# FPGA_NonIO.net
KiCad netlist of a schematic drawn in Altium Designer
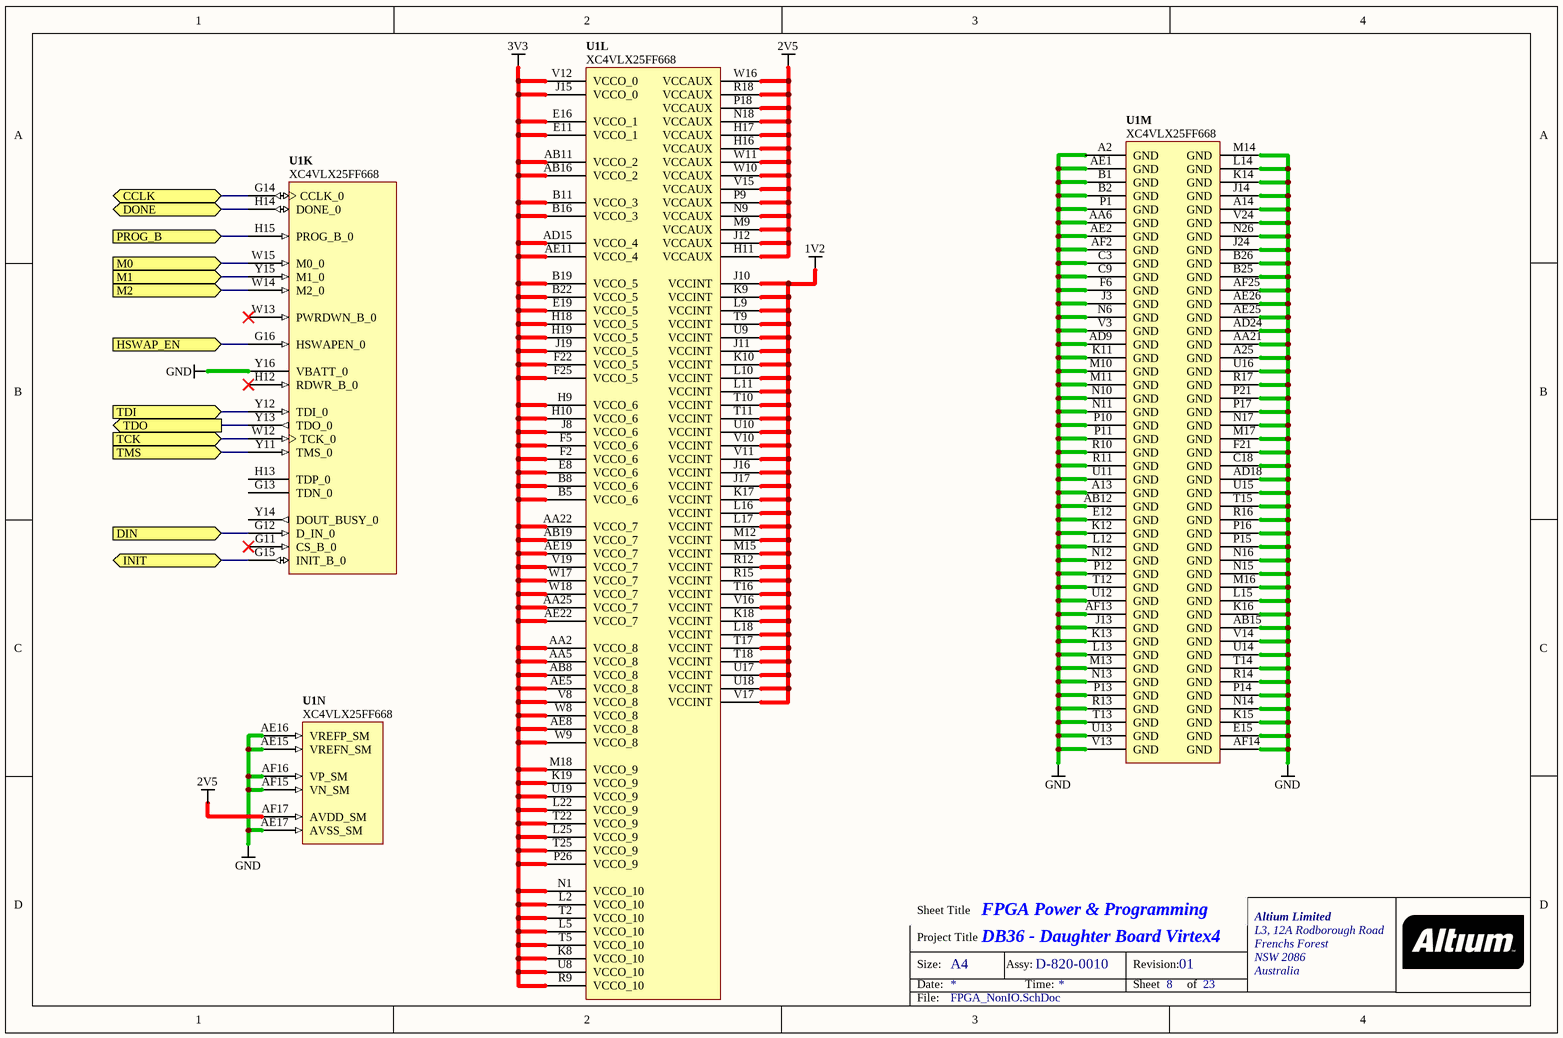
[diagram p0: FPGA_NonIO.SchDoc]

(export (version "E")
  (design (tool "Eeschema 10.0.6"))
  (components
    (comp (ref "U1")
      (value "XC4VLX25FF668")
      (footprint "XC4VLX25-10FF668C")
      (description "FPGA, Xilinx Virtex-4, XC4VLX25")
      (libsource (lib "AltiumDesignLibrary") (part "XC4VLX25-10FF668C"))
    )
  )
  (nets
    (net (code "1") (name "/CCLK") (class "Default")
      (node (ref "U1") (pin "G14") (pinfunction "CCLK_0_G14") (pintype "bidirectional"))
    )
    (net (code "2") (name "/DIN") (class "Default")
      (node (ref "U1") (pin "G12") (pinfunction "D_IN_0_G12") (pintype "input"))
    )
    (net (code "3") (name "/DONE") (class "Default")
      (node (ref "U1") (pin "H14") (pinfunction "DONE_0_H14") (pintype "bidirectional"))
    )
    (net (code "4") (name "/HSWAP_EN") (class "Default")
      (node (ref "U1") (pin "G16") (pinfunction "HSWAPEN_0_G16") (pintype "input"))
    )
    (net (code "5") (name "/INIT") (class "Default")
      (node (ref "U1") (pin "G15") (pinfunction "INIT_B_0_G15") (pintype "bidirectional"))
    )
    (net (code "6") (name "/M0") (class "Default")
      (node (ref "U1") (pin "W15") (pinfunction "M0_0_W15") (pintype "input"))
    )
    (net (code "7") (name "/M1") (class "Default")
      (node (ref "U1") (pin "Y15") (pinfunction "M1_0_Y15") (pintype "input"))
    )
    (net (code "8") (name "/M2") (class "Default")
      (node (ref "U1") (pin "W14") (pinfunction "M2_0_W14") (pintype "input"))
    )
    (net (code "9") (name "/PROG_B") (class "Default")
      (node (ref "U1") (pin "H15") (pinfunction "PROG_B_0_H15") (pintype "input"))
    )
    (net (code "10") (name "/TCK") (class "Default")
      (node (ref "U1") (pin "W12") (pinfunction "TCK_0_W12") (pintype "input"))
    )
    (net (code "11") (name "/TDI") (class "Default")
      (node (ref "U1") (pin "Y12") (pinfunction "TDI_0_Y12") (pintype "input"))
    )
    (net (code "12") (name "/TDO") (class "Default")
      (node (ref "U1") (pin "Y13") (pinfunction "TDO_0_Y13") (pintype "output"))
    )
    (net (code "13") (name "/TMS") (class "Default")
      (node (ref "U1") (pin "Y11") (pinfunction "TMS_0_Y11") (pintype "input"))
    )
    (net (code "14") (name "1V2") (class "Default")
      (node (ref "U1") (pin "J10") (pinfunction "VCCINT_J10") (pintype "power_in"))
      (node (ref "U1") (pin "J11") (pinfunction "VCCINT_J11") (pintype "power_in"))
      (node (ref "U1") (pin "J16") (pinfunction "VCCINT_J16") (pintype "power_in"))
      (node (ref "U1") (pin "J17") (pinfunction "VCCINT_J17") (pintype "power_in"))
      (node (ref "U1") (pin "K10") (pinfunction "VCCINT_K10") (pintype "power_in"))
      (node (ref "U1") (pin "K17") (pinfunction "VCCINT_K17") (pintype "power_in"))
      (node (ref "U1") (pin "K18") (pinfunction "VCCINT_K18") (pintype "power_in"))
      (node (ref "U1") (pin "K9") (pinfunction "VCCINT_K9") (pintype "power_in"))
      (node (ref "U1") (pin "L10") (pinfunction "VCCINT_L10") (pintype "power_in"))
      (node (ref "U1") (pin "L11") (pinfunction "VCCINT_L11") (pintype "power_in"))
      (node (ref "U1") (pin "L16") (pinfunction "VCCINT_L16") (pintype "power_in"))
      (node (ref "U1") (pin "L17") (pinfunction "VCCINT_L17") (pintype "power_in"))
      (node (ref "U1") (pin "L18") (pinfunction "VCCINT_L18") (pintype "power_in"))
      (node (ref "U1") (pin "L9") (pinfunction "VCCINT_L9") (pintype "power_in"))
      (node (ref "U1") (pin "M12") (pinfunction "VCCINT_M12") (pintype "power_in"))
      (node (ref "U1") (pin "M15") (pinfunction "VCCINT_M15") (pintype "power_in"))
      (node (ref "U1") (pin "R12") (pinfunction "VCCINT_R12") (pintype "power_in"))
      (node (ref "U1") (pin "R15") (pinfunction "VCCINT_R15") (pintype "power_in"))
      (node (ref "U1") (pin "T10") (pinfunction "VCCINT_T10") (pintype "power_in"))
      (node (ref "U1") (pin "T11") (pinfunction "VCCINT_T11") (pintype "power_in"))
      (node (ref "U1") (pin "T16") (pinfunction "VCCINT_T16") (pintype "power_in"))
      (node (ref "U1") (pin "T17") (pinfunction "VCCINT_T17") (pintype "power_in"))
      (node (ref "U1") (pin "T18") (pinfunction "VCCINT_T18") (pintype "power_in"))
      (node (ref "U1") (pin "T9") (pinfunction "VCCINT_T9") (pintype "power_in"))
      (node (ref "U1") (pin "U10") (pinfunction "VCCINT_U10") (pintype "power_in"))
      (node (ref "U1") (pin "U17") (pinfunction "VCCINT_U17") (pintype "power_in"))
      (node (ref "U1") (pin "U18") (pinfunction "VCCINT_U18") (pintype "power_in"))
      (node (ref "U1") (pin "U9") (pinfunction "VCCINT_U9") (pintype "power_in"))
      (node (ref "U1") (pin "V10") (pinfunction "VCCINT_V10") (pintype "power_in"))
      (node (ref "U1") (pin "V11") (pinfunction "VCCINT_V11") (pintype "power_in"))
      (node (ref "U1") (pin "V16") (pinfunction "VCCINT_V16") (pintype "power_in"))
      (node (ref "U1") (pin "V17") (pinfunction "VCCINT_V17") (pintype "power_in"))
    )
    (net (code "15") (name "2V5") (class "Default")
      (node (ref "U1") (pin "AF17") (pinfunction "AVDD_SM_AF17") (pintype "input"))
      (node (ref "U1") (pin "H11") (pinfunction "VCCAUX_H11") (pintype "power_in"))
      (node (ref "U1") (pin "H16") (pinfunction "VCCAUX_H16") (pintype "power_in"))
      (node (ref "U1") (pin "H17") (pinfunction "VCCAUX_H17") (pintype "power_in"))
      (node (ref "U1") (pin "J12") (pinfunction "VCCAUX_J12") (pintype "power_in"))
      (node (ref "U1") (pin "M9") (pinfunction "VCCAUX_M9") (pintype "power_in"))
      (node (ref "U1") (pin "N18") (pinfunction "VCCAUX_N18") (pintype "power_in"))
      (node (ref "U1") (pin "N9") (pinfunction "VCCAUX_N9") (pintype "power_in"))
      (node (ref "U1") (pin "P18") (pinfunction "VCCAUX_P18") (pintype "power_in"))
      (node (ref "U1") (pin "P9") (pinfunction "VCCAUX_P9") (pintype "power_in"))
      (node (ref "U1") (pin "R18") (pinfunction "VCCAUX_R18") (pintype "power_in"))
      (node (ref "U1") (pin "V15") (pinfunction "VCCAUX_V15") (pintype "power_in"))
      (node (ref "U1") (pin "W10") (pinfunction "VCCAUX_W10") (pintype "power_in"))
      (node (ref "U1") (pin "W11") (pinfunction "VCCAUX_W11") (pintype "power_in"))
      (node (ref "U1") (pin "W16") (pinfunction "VCCAUX_W16") (pintype "power_in"))
    )
    (net (code "16") (name "3V3") (class "Default")
      (node (ref "U1") (pin "AA2") (pinfunction "VCCO_8_AA2") (pintype "power_in"))
      (node (ref "U1") (pin "AA22") (pinfunction "VCCO_7_AA22") (pintype "power_in"))
      (node (ref "U1") (pin "AA25") (pinfunction "VCCO_7_AA25") (pintype "power_in"))
      (node (ref "U1") (pin "AA5") (pinfunction "VCCO_8_AA5") (pintype "power_in"))
      (node (ref "U1") (pin "AB11") (pinfunction "VCCO_2_AB11") (pintype "power_in"))
      (node (ref "U1") (pin "AB16") (pinfunction "VCCO_2_AB16") (pintype "power_in"))
      (node (ref "U1") (pin "AB19") (pinfunction "VCCO_7_AB19") (pintype "power_in"))
      (node (ref "U1") (pin "AB8") (pinfunction "VCCO_8_AB8") (pintype "power_in"))
      (node (ref "U1") (pin "AD15") (pinfunction "VCCO_4_AD15") (pintype "power_in"))
      (node (ref "U1") (pin "AE11") (pinfunction "VCCO_4_AE11") (pintype "power_in"))
      (node (ref "U1") (pin "AE19") (pinfunction "VCCO_7_AE19") (pintype "power_in"))
      (node (ref "U1") (pin "AE22") (pinfunction "VCCO_7_AE22") (pintype "power_in"))
      (node (ref "U1") (pin "AE5") (pinfunction "VCCO_8_AE5") (pintype "power_in"))
      (node (ref "U1") (pin "AE8") (pinfunction "VCCO_8_AE8") (pintype "power_in"))
      (node (ref "U1") (pin "B11") (pinfunction "VCCO_3_B11") (pintype "power_in"))
      (node (ref "U1") (pin "B16") (pinfunction "VCCO_3_B16") (pintype "power_in"))
      (node (ref "U1") (pin "B19") (pinfunction "VCCO_5_B19") (pintype "power_in"))
      (node (ref "U1") (pin "B22") (pinfunction "VCCO_5_B22") (pintype "power_in"))
      (node (ref "U1") (pin "B5") (pinfunction "VCCO_6_B5") (pintype "power_in"))
      (node (ref "U1") (pin "B8") (pinfunction "VCCO_6_B8") (pintype "power_in"))
      (node (ref "U1") (pin "E11") (pinfunction "VCCO_1_E11") (pintype "power_in"))
      (node (ref "U1") (pin "E16") (pinfunction "VCCO_1_E16") (pintype "power_in"))
      (node (ref "U1") (pin "E19") (pinfunction "VCCO_5_E19") (pintype "power_in"))
      (node (ref "U1") (pin "E8") (pinfunction "VCCO_6_E8") (pintype "power_in"))
      (node (ref "U1") (pin "F2") (pinfunction "VCCO_6_F2") (pintype "power_in"))
      (node (ref "U1") (pin "F22") (pinfunction "VCCO_5_F22") (pintype "power_in"))
      (node (ref "U1") (pin "F25") (pinfunction "VCCO_5_F25") (pintype "power_in"))
      (node (ref "U1") (pin "F5") (pinfunction "VCCO_6_F5") (pintype "power_in"))
      (node (ref "U1") (pin "H10") (pinfunction "VCCO_6_H10") (pintype "power_in"))
      (node (ref "U1") (pin "H18") (pinfunction "VCCO_5_H18") (pintype "power_in"))
      (node (ref "U1") (pin "H19") (pinfunction "VCCO_5_H19") (pintype "power_in"))
      (node (ref "U1") (pin "H9") (pinfunction "VCCO_6_H9") (pintype "power_in"))
      (node (ref "U1") (pin "J15") (pinfunction "VCCO_0_J15") (pintype "power_in"))
      (node (ref "U1") (pin "J19") (pinfunction "VCCO_5_J19") (pintype "power_in"))
      (node (ref "U1") (pin "J8") (pinfunction "VCCO_6_J8") (pintype "power_in"))
      (node (ref "U1") (pin "K19") (pinfunction "VCCO_9_K19") (pintype "power_in"))
      (node (ref "U1") (pin "K8") (pinfunction "VCCO_10_K8") (pintype "power_in"))
      (node (ref "U1") (pin "L2") (pinfunction "VCCO_10_L2") (pintype "power_in"))
      (node (ref "U1") (pin "L22") (pinfunction "VCCO_9_L22") (pintype "power_in"))
      (node (ref "U1") (pin "L25") (pinfunction "VCCO_9_L25") (pintype "power_in"))
      (node (ref "U1") (pin "L5") (pinfunction "VCCO_10_L5") (pintype "power_in"))
      (node (ref "U1") (pin "M18") (pinfunction "VCCO_9_M18") (pintype "power_in"))
      (node (ref "U1") (pin "N1") (pinfunction "VCCO_10_N1") (pintype "power_in"))
      (node (ref "U1") (pin "P26") (pinfunction "VCCO_9_P26") (pintype "power_in"))
      (node (ref "U1") (pin "R9") (pinfunction "VCCO_10_R9") (pintype "power_in"))
      (node (ref "U1") (pin "T2") (pinfunction "VCCO_10_T2") (pintype "power_in"))
      (node (ref "U1") (pin "T22") (pinfunction "VCCO_9_T22") (pintype "power_in"))
      (node (ref "U1") (pin "T25") (pinfunction "VCCO_9_T25") (pintype "power_in"))
      (node (ref "U1") (pin "T5") (pinfunction "VCCO_10_T5") (pintype "power_in"))
      (node (ref "U1") (pin "U19") (pinfunction "VCCO_9_U19") (pintype "power_in"))
      (node (ref "U1") (pin "U8") (pinfunction "VCCO_10_U8") (pintype "power_in"))
      (node (ref "U1") (pin "V12") (pinfunction "VCCO_0_V12") (pintype "power_in"))
      (node (ref "U1") (pin "V19") (pinfunction "VCCO_7_V19") (pintype "power_in"))
      (node (ref "U1") (pin "V8") (pinfunction "VCCO_8_V8") (pintype "power_in"))
      (node (ref "U1") (pin "W17") (pinfunction "VCCO_7_W17") (pintype "power_in"))
      (node (ref "U1") (pin "W18") (pinfunction "VCCO_7_W18") (pintype "power_in"))
      (node (ref "U1") (pin "W8") (pinfunction "VCCO_8_W8") (pintype "power_in"))
      (node (ref "U1") (pin "W9") (pinfunction "VCCO_8_W9") (pintype "power_in"))
    )
    (net (code "17") (name "GND") (class "Default")
      (node (ref "U1") (pin "A13") (pinfunction "GND_A13") (pintype "power_in"))
      (node (ref "U1") (pin "A14") (pinfunction "GND_A14") (pintype "power_in"))
      (node (ref "U1") (pin "A2") (pinfunction "GND_A2") (pintype "power_in"))
      (node (ref "U1") (pin "A25") (pinfunction "GND_A25") (pintype "power_in"))
      (node (ref "U1") (pin "AA21") (pinfunction "GND_AA21") (pintype "power_in"))
      (node (ref "U1") (pin "AA6") (pinfunction "GND_AA6") (pintype "power_in"))
      (node (ref "U1") (pin "AB12") (pinfunction "GND_AB12") (pintype "power_in"))
      (node (ref "U1") (pin "AB15") (pinfunction "GND_AB15") (pintype "power_in"))
      (node (ref "U1") (pin "AD18") (pinfunction "GND_AD18") (pintype "power_in"))
      (node (ref "U1") (pin "AD24") (pinfunction "GND_AD24") (pintype "power_in"))
      (node (ref "U1") (pin "AD9") (pinfunction "GND_AD9") (pintype "power_in"))
      (node (ref "U1") (pin "AE1") (pinfunction "GND_AE1") (pintype "power_in"))
      (node (ref "U1") (pin "AE15") (pinfunction "VREFN_SM_AE15") (pintype "input"))
      (node (ref "U1") (pin "AE16") (pinfunction "VREFP_SM_AE16") (pintype "input"))
      (node (ref "U1") (pin "AE17") (pinfunction "AVSS_SM_AE17") (pintype "input"))
      (node (ref "U1") (pin "AE2") (pinfunction "GND_AE2") (pintype "power_in"))
      (node (ref "U1") (pin "AE25") (pinfunction "GND_AE25") (pintype "power_in"))
      (node (ref "U1") (pin "AE26") (pinfunction "GND_AE26") (pintype "power_in"))
      (node (ref "U1") (pin "AF13") (pinfunction "GND_AF13") (pintype "power_in"))
      (node (ref "U1") (pin "AF14") (pinfunction "GND_AF14") (pintype "power_in"))
      (node (ref "U1") (pin "AF15") (pinfunction "VN_SM_AF15") (pintype "input"))
      (node (ref "U1") (pin "AF16") (pinfunction "VP_SM_AF16") (pintype "input"))
      (node (ref "U1") (pin "AF2") (pinfunction "GND_AF2") (pintype "power_in"))
      (node (ref "U1") (pin "AF25") (pinfunction "GND_AF25") (pintype "power_in"))
      (node (ref "U1") (pin "B1") (pinfunction "GND_B1") (pintype "power_in"))
      (node (ref "U1") (pin "B2") (pinfunction "GND_B2") (pintype "power_in"))
      (node (ref "U1") (pin "B25") (pinfunction "GND_B25") (pintype "power_in"))
      (node (ref "U1") (pin "B26") (pinfunction "GND_B26") (pintype "power_in"))
      (node (ref "U1") (pin "C18") (pinfunction "GND_C18") (pintype "power_in"))
      (node (ref "U1") (pin "C3") (pinfunction "GND_C3") (pintype "power_in"))
      (node (ref "U1") (pin "C9") (pinfunction "GND_C9") (pintype "power_in"))
      (node (ref "U1") (pin "E12") (pinfunction "GND_E12") (pintype "power_in"))
      (node (ref "U1") (pin "E15") (pinfunction "GND_E15") (pintype "power_in"))
      (node (ref "U1") (pin "F21") (pinfunction "GND_F21") (pintype "power_in"))
      (node (ref "U1") (pin "F6") (pinfunction "GND_F6") (pintype "power_in"))
      (node (ref "U1") (pin "J13") (pinfunction "GND_J13") (pintype "power_in"))
      (node (ref "U1") (pin "J14") (pinfunction "GND_J14") (pintype "power_in"))
      (node (ref "U1") (pin "J24") (pinfunction "GND_J24") (pintype "power_in"))
      (node (ref "U1") (pin "J3") (pinfunction "GND_J3") (pintype "power_in"))
      (node (ref "U1") (pin "K11") (pinfunction "GND_K11") (pintype "power_in"))
      (node (ref "U1") (pin "K12") (pinfunction "GND_K12") (pintype "power_in"))
      (node (ref "U1") (pin "K13") (pinfunction "GND_K13") (pintype "power_in"))
      (node (ref "U1") (pin "K14") (pinfunction "GND_K14") (pintype "power_in"))
      (node (ref "U1") (pin "K15") (pinfunction "GND_K15") (pintype "power_in"))
      (node (ref "U1") (pin "K16") (pinfunction "GND_K16") (pintype "power_in"))
      (node (ref "U1") (pin "L12") (pinfunction "GND_L12") (pintype "power_in"))
      (node (ref "U1") (pin "L13") (pinfunction "GND_L13") (pintype "power_in"))
      (node (ref "U1") (pin "L14") (pinfunction "GND_L14") (pintype "power_in"))
      (node (ref "U1") (pin "L15") (pinfunction "GND_L15") (pintype "power_in"))
      (node (ref "U1") (pin "M10") (pinfunction "GND_M10") (pintype "power_in"))
      (node (ref "U1") (pin "M11") (pinfunction "GND_M11") (pintype "power_in"))
      (node (ref "U1") (pin "M13") (pinfunction "GND_M13") (pintype "power_in"))
      (node (ref "U1") (pin "M14") (pinfunction "GND_M14") (pintype "power_in"))
      (node (ref "U1") (pin "M16") (pinfunction "GND_M16") (pintype "power_in"))
      (node (ref "U1") (pin "M17") (pinfunction "GND_M17") (pintype "power_in"))
      (node (ref "U1") (pin "N10") (pinfunction "GND_N10") (pintype "power_in"))
      (node (ref "U1") (pin "N11") (pinfunction "GND_N11") (pintype "power_in"))
      (node (ref "U1") (pin "N12") (pinfunction "GND_N12") (pintype "power_in"))
      (node (ref "U1") (pin "N13") (pinfunction "GND_N13") (pintype "power_in"))
      (node (ref "U1") (pin "N14") (pinfunction "GND_N14") (pintype "power_in"))
      (node (ref "U1") (pin "N15") (pinfunction "GND_N15") (pintype "power_in"))
      (node (ref "U1") (pin "N16") (pinfunction "GND_N16") (pintype "power_in"))
      (node (ref "U1") (pin "N17") (pinfunction "GND_N17") (pintype "power_in"))
      (node (ref "U1") (pin "N26") (pinfunction "GND_N26") (pintype "power_in"))
      (node (ref "U1") (pin "N6") (pinfunction "GND_N6") (pintype "power_in"))
      (node (ref "U1") (pin "P1") (pinfunction "GND_P1") (pintype "power_in"))
      (node (ref "U1") (pin "P10") (pinfunction "GND_P10") (pintype "power_in"))
      (node (ref "U1") (pin "P11") (pinfunction "GND_P11") (pintype "power_in"))
      (node (ref "U1") (pin "P12") (pinfunction "GND_P12") (pintype "power_in"))
      (node (ref "U1") (pin "P13") (pinfunction "GND_P13") (pintype "power_in"))
      (node (ref "U1") (pin "P14") (pinfunction "GND_P14") (pintype "power_in"))
      (node (ref "U1") (pin "P15") (pinfunction "GND_P15") (pintype "power_in"))
      (node (ref "U1") (pin "P16") (pinfunction "GND_P16") (pintype "power_in"))
      (node (ref "U1") (pin "P17") (pinfunction "GND_P17") (pintype "power_in"))
      (node (ref "U1") (pin "P21") (pinfunction "GND_P21") (pintype "power_in"))
      (node (ref "U1") (pin "R10") (pinfunction "GND_R10") (pintype "power_in"))
      (node (ref "U1") (pin "R11") (pinfunction "GND_R11") (pintype "power_in"))
      (node (ref "U1") (pin "R13") (pinfunction "GND_R13") (pintype "power_in"))
      (node (ref "U1") (pin "R14") (pinfunction "GND_R14") (pintype "power_in"))
      (node (ref "U1") (pin "R16") (pinfunction "GND_R16") (pintype "power_in"))
      (node (ref "U1") (pin "R17") (pinfunction "GND_R17") (pintype "power_in"))
      (node (ref "U1") (pin "T12") (pinfunction "GND_T12") (pintype "power_in"))
      (node (ref "U1") (pin "T13") (pinfunction "GND_T13") (pintype "power_in"))
      (node (ref "U1") (pin "T14") (pinfunction "GND_T14") (pintype "power_in"))
      (node (ref "U1") (pin "T15") (pinfunction "GND_T15") (pintype "power_in"))
      (node (ref "U1") (pin "U11") (pinfunction "GND_U11") (pintype "power_in"))
      (node (ref "U1") (pin "U12") (pinfunction "GND_U12") (pintype "power_in"))
      (node (ref "U1") (pin "U13") (pinfunction "GND_U13") (pintype "power_in"))
      (node (ref "U1") (pin "U14") (pinfunction "GND_U14") (pintype "power_in"))
      (node (ref "U1") (pin "U15") (pinfunction "GND_U15") (pintype "power_in"))
      (node (ref "U1") (pin "U16") (pinfunction "GND_U16") (pintype "power_in"))
      (node (ref "U1") (pin "V13") (pinfunction "GND_V13") (pintype "power_in"))
      (node (ref "U1") (pin "V14") (pinfunction "GND_V14") (pintype "power_in"))
      (node (ref "U1") (pin "V24") (pinfunction "GND_V24") (pintype "power_in"))
      (node (ref "U1") (pin "V3") (pinfunction "GND_V3") (pintype "power_in"))
      (node (ref "U1") (pin "Y16") (pinfunction "VBATT_0_Y16") (pintype "power_in"))
    )
    (net (code "18") (name "unconnected-(U1K-CS_B_0-PadG11)") (class "Default")
      (node (ref "U1") (pin "G11") (pinfunction "CS_B_0_G11") (pintype "input+no_connect"))
    )
    (net (code "19") (name "unconnected-(U1K-DOUT_BUSY_0-PadY14)") (class "Default")
      (node (ref "U1") (pin "Y14") (pinfunction "DOUT_BUSY_0_Y14") (pintype "output"))
    )
    (net (code "20") (name "unconnected-(U1K-PWRDWN_B_0-PadW13)") (class "Default")
      (node (ref "U1") (pin "W13") (pinfunction "PWRDWN_B_0_W13") (pintype "input+no_connect"))
    )
    (net (code "21") (name "unconnected-(U1K-RDWR_B_0-PadH12)") (class "Default")
      (node (ref "U1") (pin "H12") (pinfunction "RDWR_B_0_H12") (pintype "input+no_connect"))
    )
    (net (code "22") (name "unconnected-(U1K-TDN_0-PadG13)") (class "Default")
      (node (ref "U1") (pin "G13") (pinfunction "TDN_0_G13") (pintype "passive"))
    )
    (net (code "23") (name "unconnected-(U1K-TDP_0-PadH13)") (class "Default")
      (node (ref "U1") (pin "H13") (pinfunction "TDP_0_H13") (pintype "passive"))
    )
  )
)
